# GDT_DRIVER.net
KiCad netlist of a schematic drawn in EAGLE
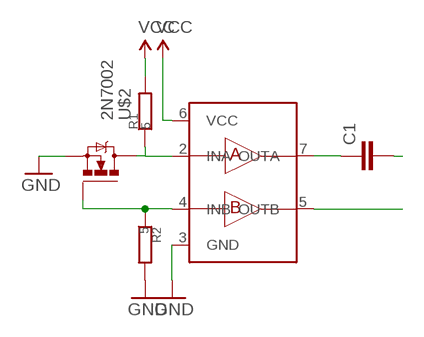
[diagram p0: schematic, sheet 1]

(export (version "E")
  (design (tool "Eeschema 10.0.6"))
  (components
    (comp (ref "C1")
      (value "CAP1210")
      (footprint "eagle-import:1210")
      (libsource (lib "eagle-import") (part "CAP1210"))
    )
    (comp (ref "R1")
      (value "5")
      (footprint "eagle-import:R0805")
      (libsource (lib "eagle-import") (part "R0805"))
    )
    (comp (ref "R2")
      (value "5")
      (footprint "eagle-import:R0805")
      (libsource (lib "eagle-import") (part "R0805"))
    )
    (comp (ref "U$1")
      (value "INDN602")
      (footprint "eagle-import:SO08")
      (libsource (lib "eagle-import") (part "INDN602"))
    )
    (comp (ref "U$2")
      (value "2N7002")
      (footprint "eagle-import:SOT23")
      (libsource (lib "eagle-import") (part "2N7002"))
    )
  )
  (nets
    (net (code "1") (name "GND") (class "Default")
      (node (ref "R2") (pin "2") (pinfunction "2_2") (pintype "passive"))
      (node (ref "U$1") (pin "3") (pinfunction "GND_3") (pintype "bidirectional"))
      (node (ref "U$2") (pin "2") (pinfunction "S_2") (pintype "passive"))
    )
    (net (code "2") (name "Net-(U$1-INA)") (class "Default")
      (node (ref "R1") (pin "1") (pinfunction "1_1") (pintype "passive"))
      (node (ref "U$1") (pin "2") (pinfunction "INA_2") (pintype "bidirectional"))
      (node (ref "U$2") (pin "3") (pinfunction "D_3") (pintype "passive"))
    )
    (net (code "3") (name "Net-(U$1-INB)") (class "Default")
      (node (ref "R2") (pin "1") (pinfunction "1_1") (pintype "passive"))
      (node (ref "U$1") (pin "4") (pinfunction "INB_4") (pintype "bidirectional"))
      (node (ref "U$2") (pin "1") (pinfunction "G_1") (pintype "passive"))
    )
    (net (code "4") (name "Net-(U$1-OUTA)") (class "Default")
      (node (ref "C1") (pin "1") (pinfunction "1_1") (pintype "passive"))
      (node (ref "U$1") (pin "7") (pinfunction "OUTA_7") (pintype "bidirectional"))
    )
    (net (code "5") (name "VCC") (class "Default")
      (node (ref "R1") (pin "2") (pinfunction "2_2") (pintype "passive"))
      (node (ref "U$1") (pin "6") (pinfunction "VCC_6") (pintype "bidirectional"))
    )
    (net (code "6") (name "unconnected-(C1-Pad2)") (class "Default")
      (node (ref "C1") (pin "2") (pinfunction "2_2") (pintype "passive"))
    )
    (net (code "7") (name "unconnected-(U$1-OUTB-Pad5)") (class "Default")
      (node (ref "U$1") (pin "5") (pinfunction "OUTB_5") (pintype "bidirectional"))
    )
  )
)
